# PCB_Telemetria_2020.net
KiCad netlist of a schematic drawn in EAGLE
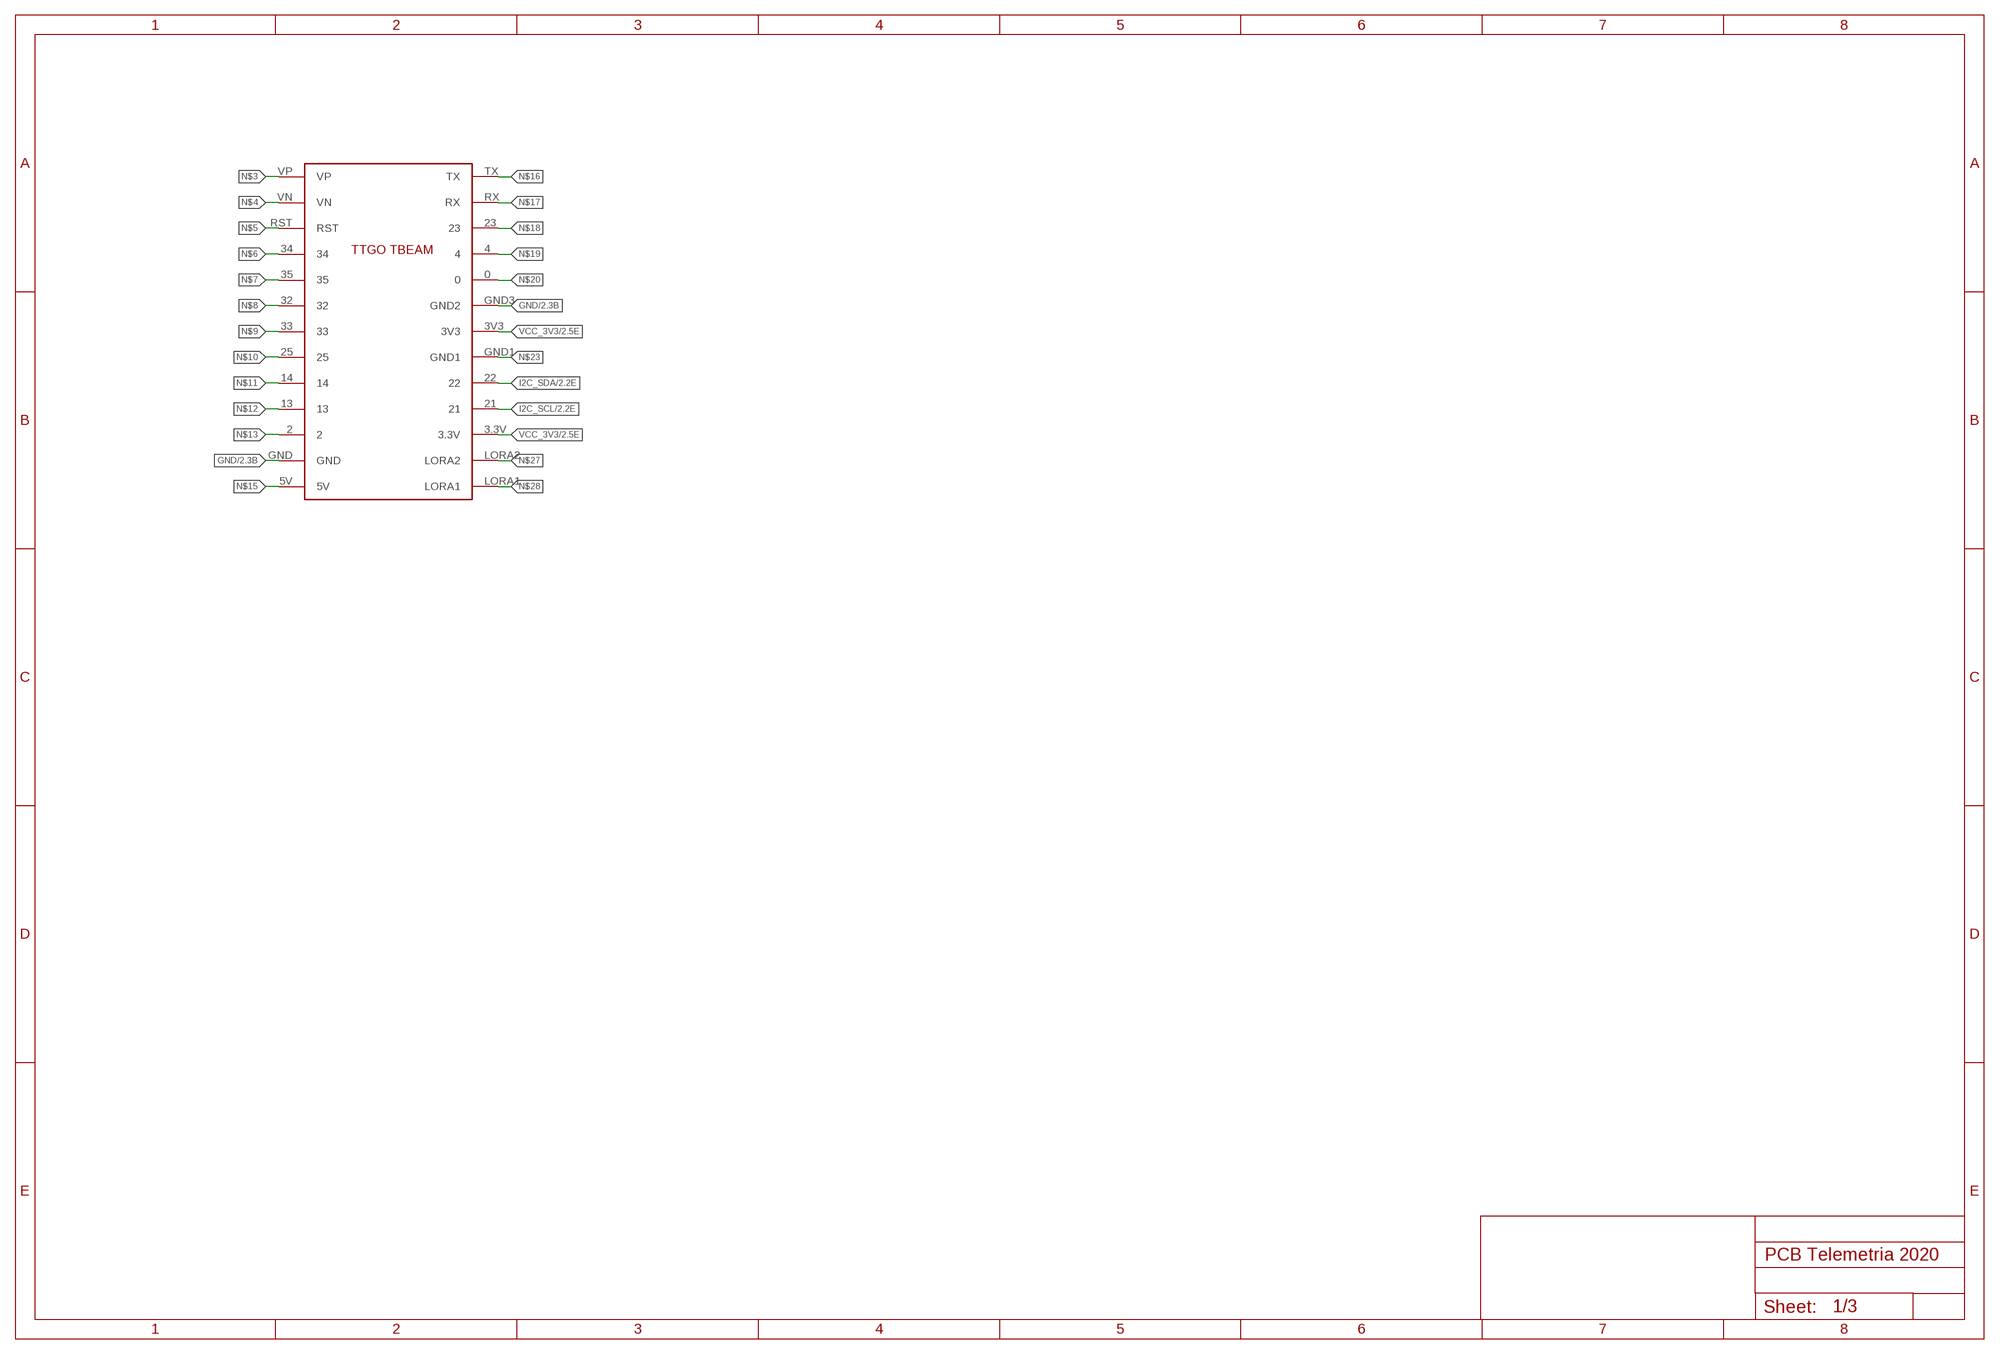
[diagram p0: schematic, sheet 1]
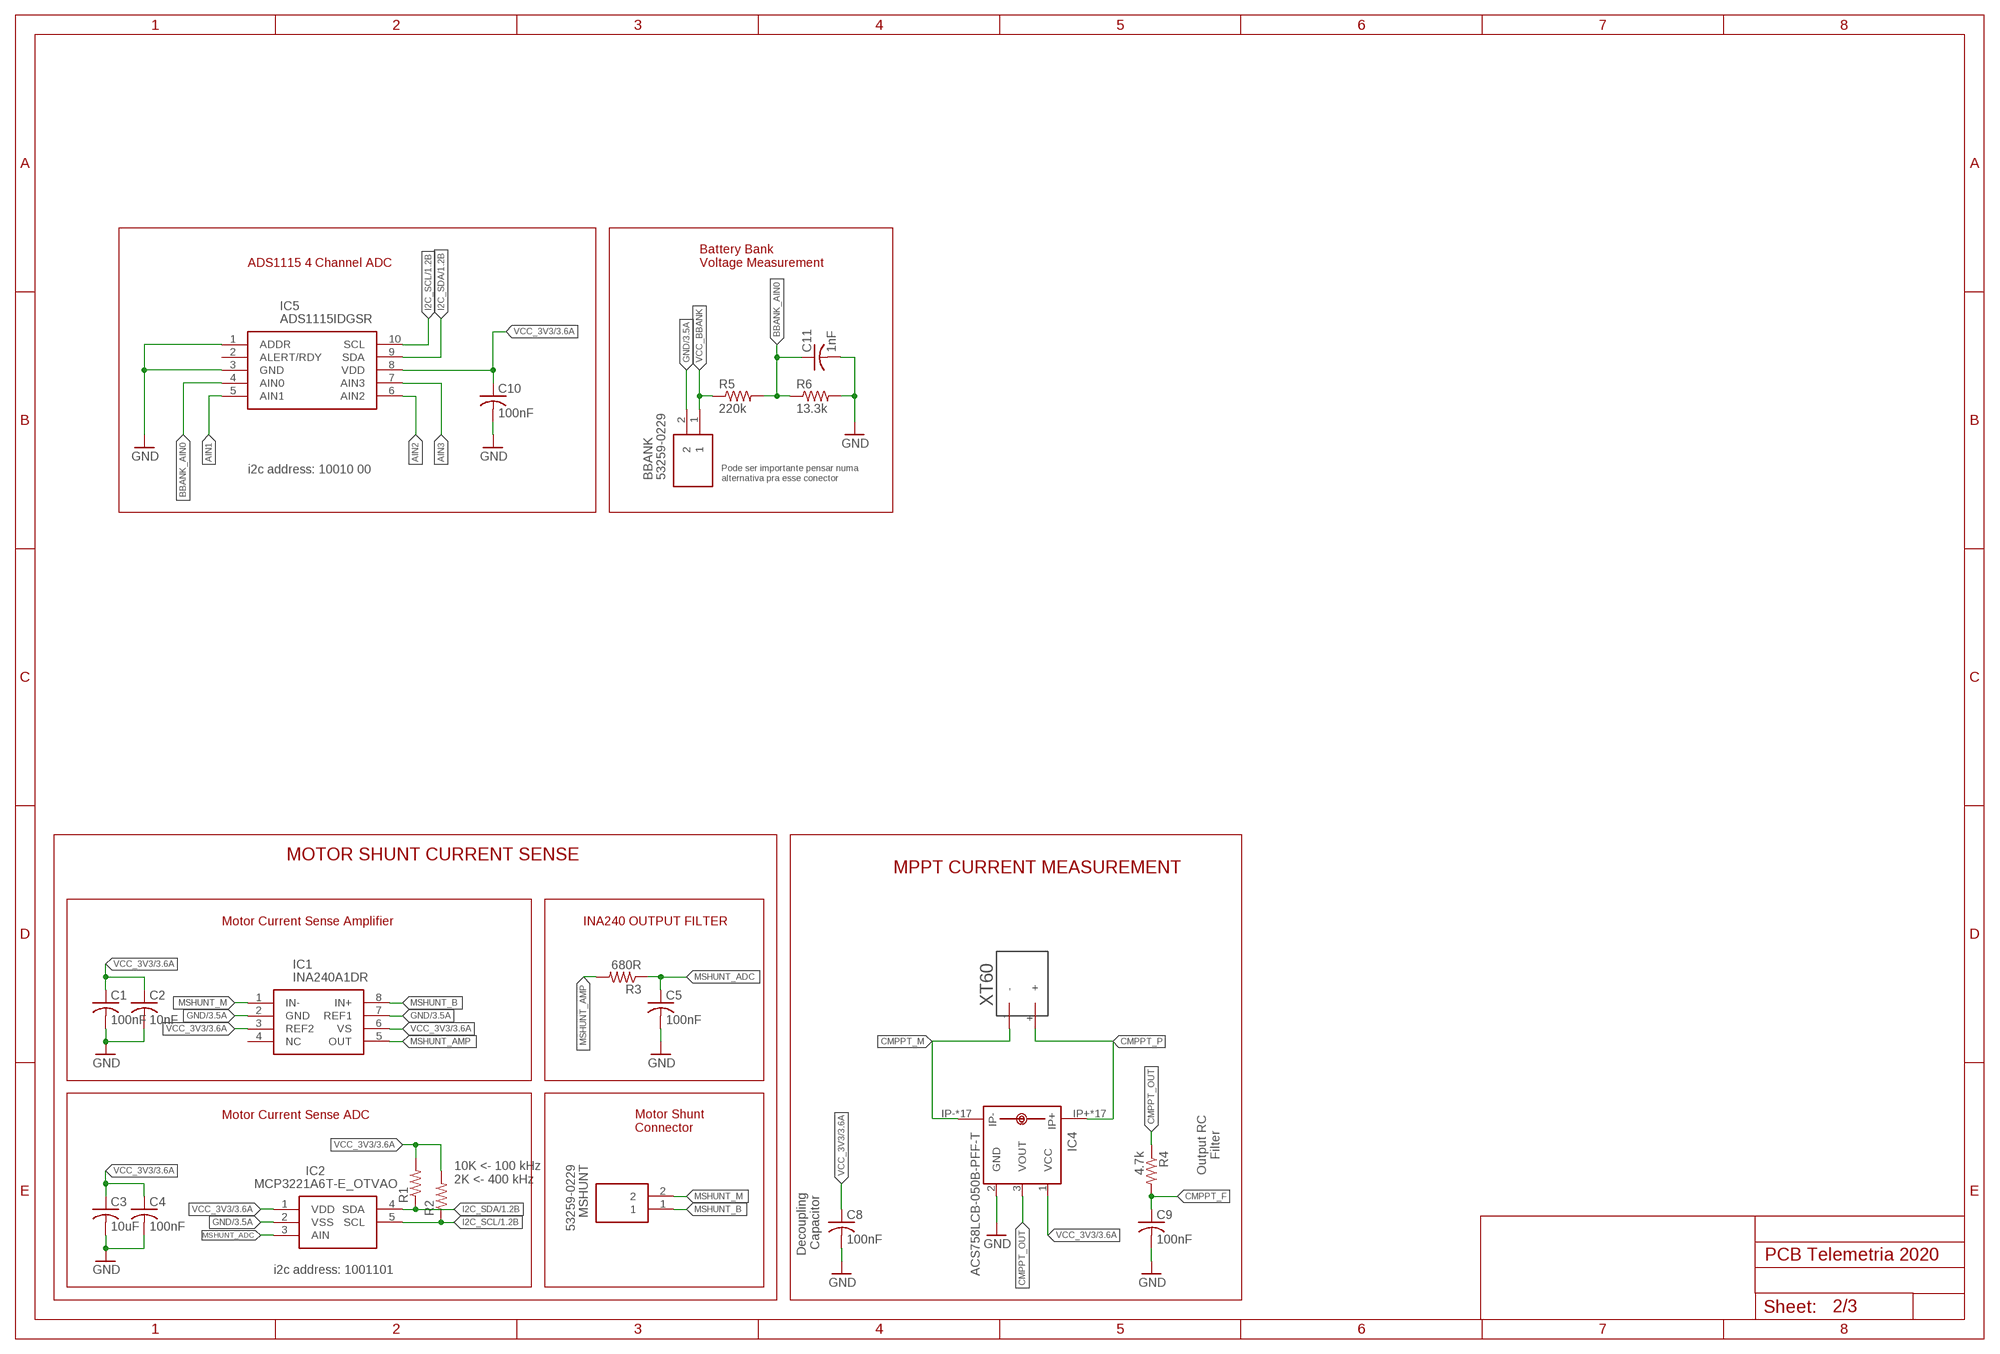
[diagram p1: schematic, sheet 2]
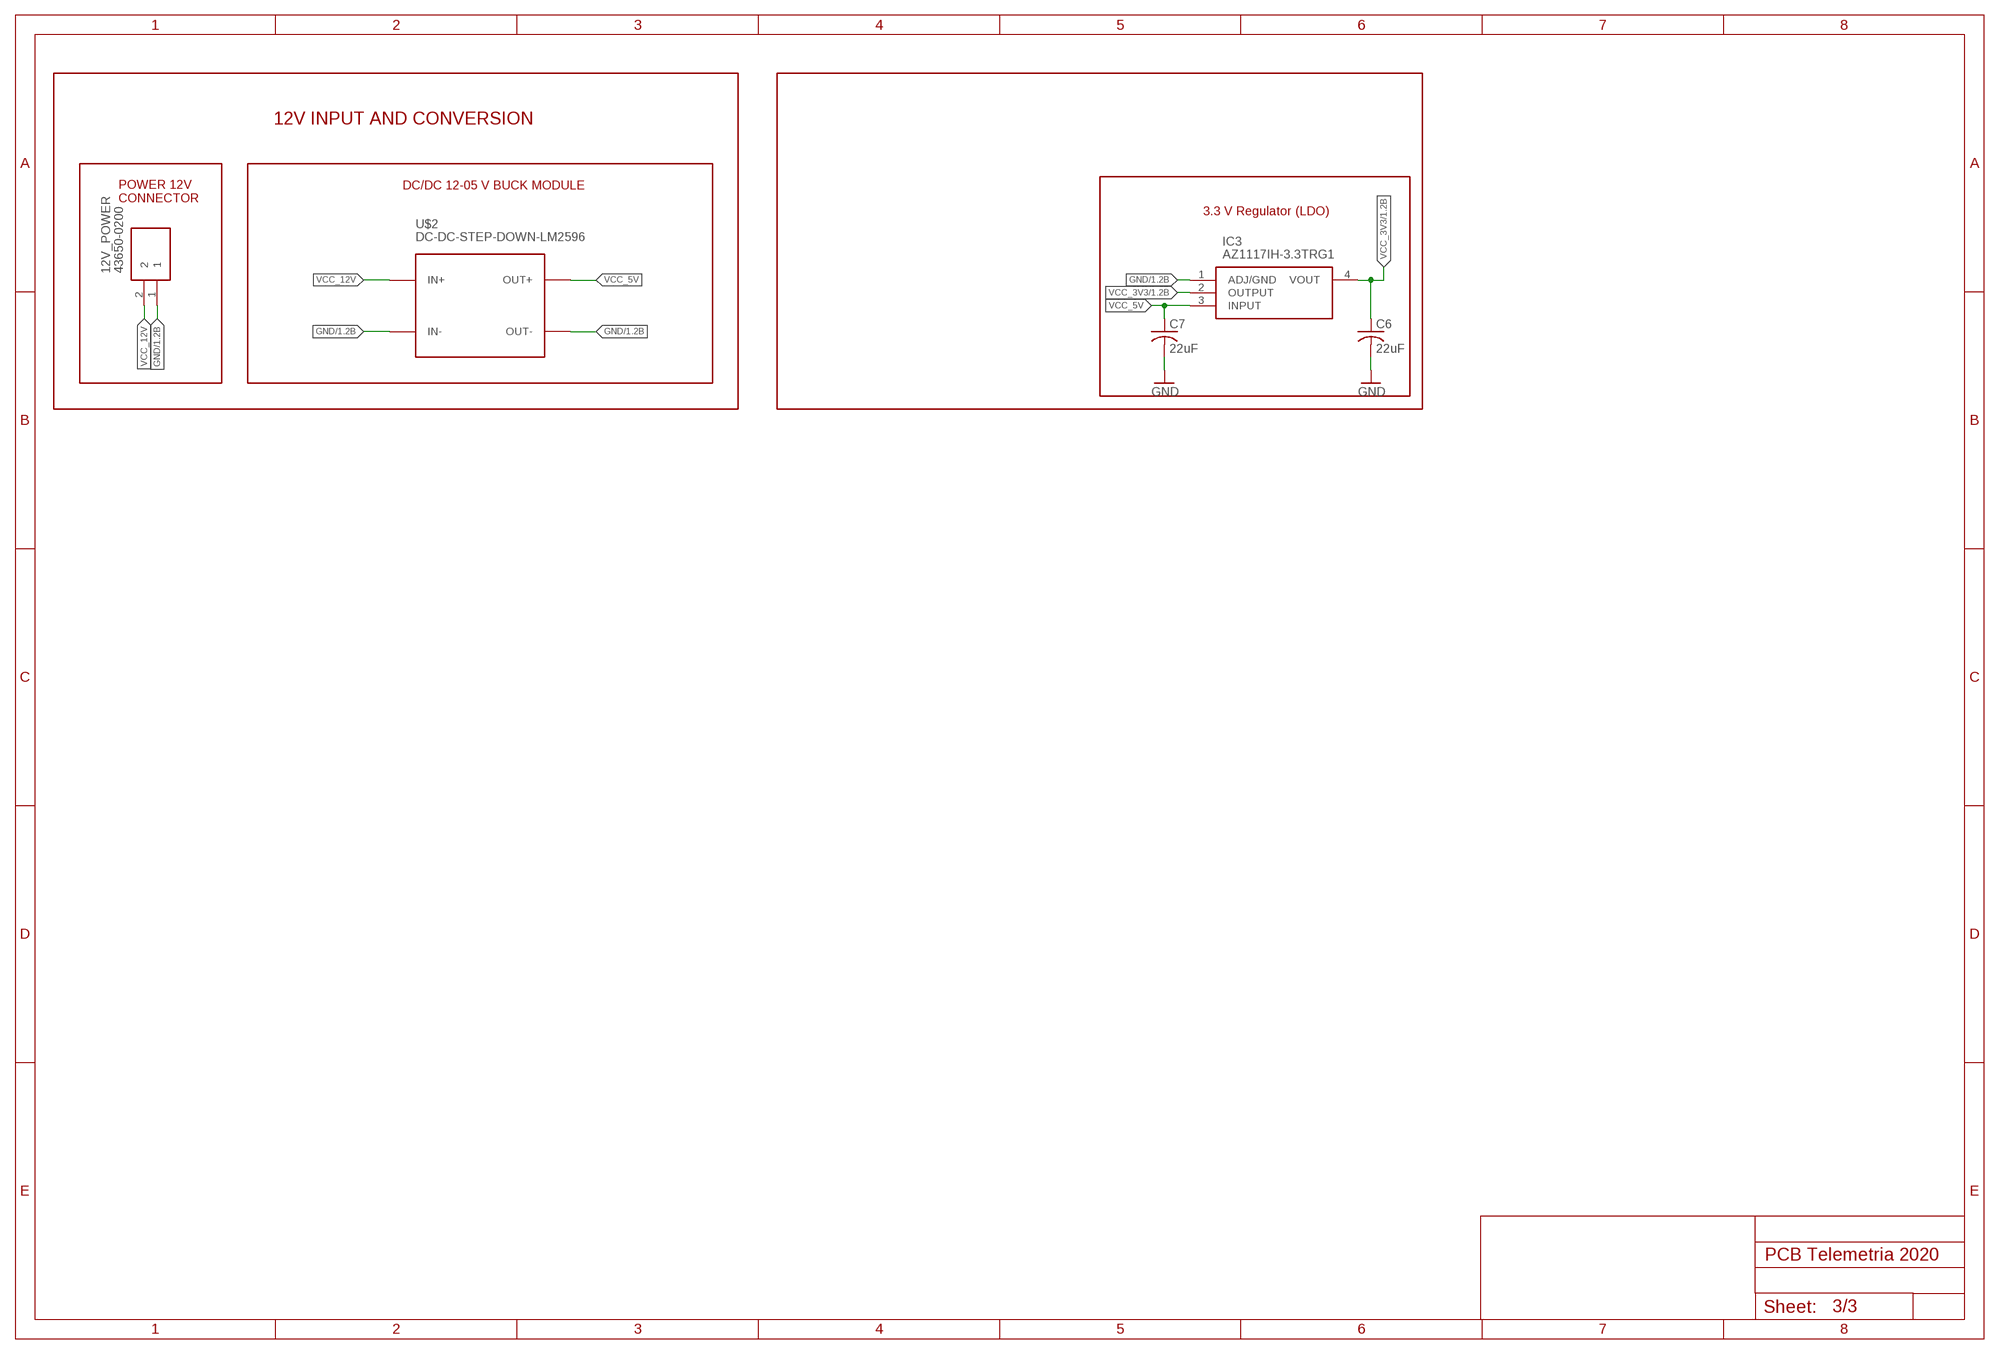
[diagram p2: schematic, sheet 3]

(export (version "E")
  (design (tool "Eeschema 10.0.6"))
  (components
    (comp (ref "12V_POWER")
      (value "43650-0200")
      (footprint "eagle-import:43650-0200")
      (fields (field (name "MOUSER_PART_NUMBER") "538-43650-0200"))
      (libsource (lib "eagle-import") (part "43650-0200"))
    )
    (comp (ref "C6")
      (value "22uF")
      (footprint "eagle-import:C0805")
      (libsource (lib "eagle-import") (part "C-USC0805"))
    )
    (comp (ref "C7")
      (value "22uF")
      (footprint "eagle-import:C0805")
      (libsource (lib "eagle-import") (part "C-USC0805"))
    )
    (comp (ref "IC3")
      (value "AZ1117IH-3.3TRG1")
      (footprint "eagle-import:SOT230P700X170-4N")
      (fields (field (name "MOUSER_PART_NUMBER") "621-AZ1117IH-3.3TRG1"))
      (libsource (lib "eagle-import") (part "AZ1117IH-3.3TRG1"))
    )
    (comp (ref "U$2")
      (value "DC-DC-STEP-DOWN-LM2596")
      (footprint "eagle-import:DC-DC-STEP-DOWN-LM2596")
      (libsource (lib "eagle-import") (part "DC-DC-STEP-DOWN-LM2596"))
    )
    (comp (ref "BBANK")
      (value "53259-0229")
      (footprint "eagle-import:0532590229")
      (fields (field (name "MOUSER_PART_NUMBER") "538-53259-0229"))
      (libsource (lib "eagle-import") (part "53259-0229"))
    )
    (comp (ref "C1")
      (value "100nF")
      (footprint "eagle-import:C0805")
      (libsource (lib "eagle-import") (part "C-USC0805"))
    )
    (comp (ref "C2")
      (value "10nF")
      (footprint "eagle-import:C0805")
      (libsource (lib "eagle-import") (part "C-USC0805"))
    )
    (comp (ref "C3")
      (value "10uF")
      (footprint "eagle-import:C0805")
      (libsource (lib "eagle-import") (part "C-USC0805"))
    )
    (comp (ref "C4")
      (value "100nF")
      (footprint "eagle-import:C0805")
      (libsource (lib "eagle-import") (part "C-USC0805"))
    )
    (comp (ref "C5")
      (value "100nF")
      (footprint "eagle-import:C0805")
      (libsource (lib "eagle-import") (part "C-USC0805"))
    )
    (comp (ref "C8")
      (value "100nF")
      (footprint "eagle-import:C0805")
      (libsource (lib "eagle-import") (part "C-USC0805"))
    )
    (comp (ref "C9")
      (value "100nF")
      (footprint "eagle-import:C0805")
      (libsource (lib "eagle-import") (part "C-USC0805"))
    )
    (comp (ref "C10")
      (value "100nF")
      (footprint "eagle-import:C0805")
      (libsource (lib "eagle-import") (part "C-USC0805"))
    )
    (comp (ref "C11")
      (value "1nF")
      (footprint "eagle-import:C0805")
      (libsource (lib "eagle-import") (part "C-USC0805"))
    )
    (comp (ref "IC1")
      (value "INA240A1DR")
      (footprint "eagle-import:SOIC127P600X175-8N")
      (fields (field (name "MOUSER_PART_NUMBER") "595-INA240A1DR"))
      (libsource (lib "eagle-import") (part "INA240A1DR"))
    )
    (comp (ref "IC2")
      (value "MCP3221A6T-E_OTVAO")
      (footprint "eagle-import:SOT95P280X145-5N")
      (fields
        (field (name "MANUFACTURER_PART_NUMBER") "MCP3221A6T-E/OTVAO")
        (field (name "MOUSER_PART_NUMBER") "579-MCP3221A6TEOTVAO")
      )
      (libsource (lib "eagle-import") (part "MCP3221A6T-E_OTVAO"))
    )
    (comp (ref "IC4")
      (value "ACS758LCB-050B-PFF-T")
      (footprint "eagle-import:CB-PFF")
      (libsource (lib "eagle-import") (part "ACS758LCB-050B-PFF-T"))
    )
    (comp (ref "IC5")
      (value "ADS1115IDGSR")
      (footprint "eagle-import:SOP50P490X110-10N")
      (fields (field (name "MOUSER_PART_NUMBER") "595-ADS1115IDGSR"))
      (libsource (lib "eagle-import") (part "ADS1115IDGSR"))
    )
    (comp (ref "MSHUNT")
      (value "53259-0229")
      (footprint "eagle-import:0532590229")
      (fields (field (name "MOUSER_PART_NUMBER") "538-53259-0229"))
      (libsource (lib "eagle-import") (part "53259-0229"))
    )
    (comp (ref "R1")
      (value "R-US_R0805")
      (footprint "eagle-import:R0805")
      (libsource (lib "eagle-import") (part "R-US_R0805"))
    )
    (comp (ref "R2")
      (value "R-US_R0805")
      (footprint "eagle-import:R0805")
      (libsource (lib "eagle-import") (part "R-US_R0805"))
    )
    (comp (ref "R3")
      (value "680R")
      (footprint "eagle-import:R0805")
      (libsource (lib "eagle-import") (part "R-US_R0805"))
    )
    (comp (ref "R4")
      (value "4.7k")
      (footprint "eagle-import:R0805")
      (libsource (lib "eagle-import") (part "R-US_R0805"))
    )
    (comp (ref "R5")
      (value "220k")
      (footprint "eagle-import:R0805")
      (libsource (lib "eagle-import") (part "R-US_R0805"))
    )
    (comp (ref "R6")
      (value "13.3k")
      (footprint "eagle-import:R0805")
      (libsource (lib "eagle-import") (part "R-US_R0805"))
    )
    (comp (ref "U$3")
      (value "XT60")
      (footprint "eagle-import:XT60")
      (libsource (lib "eagle-import") (part "XT60"))
    )
    (comp (ref "U$1")
      (value "TTGOBEAM")
      (footprint "eagle-import:TTGOBEAM")
      (libsource (lib "eagle-import") (part "TTGOBEAM"))
    )
  )
  (nets
    (net (code "1") (name "AIN1") (class "Default")
      (node (ref "IC5") (pin "5") (pinfunction "AIN1_5") (pintype "bidirectional"))
    )
    (net (code "2") (name "AIN2") (class "Default")
      (node (ref "IC5") (pin "6") (pinfunction "AIN2_6") (pintype "bidirectional"))
    )
    (net (code "3") (name "AIN3") (class "Default")
      (node (ref "IC5") (pin "7") (pinfunction "AIN3_7") (pintype "bidirectional"))
    )
    (net (code "4") (name "BBANK_AIN0") (class "Default")
      (node (ref "C11") (pin "1") (pinfunction "1_1") (pintype "passive"))
      (node (ref "IC5") (pin "4") (pinfunction "AIN0_4") (pintype "bidirectional"))
      (node (ref "R5") (pin "2") (pinfunction "2_2") (pintype "passive"))
      (node (ref "R6") (pin "1") (pinfunction "1_1") (pintype "passive"))
    )
    (net (code "5") (name "CMPPT_F") (class "Default")
      (node (ref "C9") (pin "1") (pinfunction "1_1") (pintype "passive"))
      (node (ref "R4") (pin "2") (pinfunction "2_2") (pintype "passive"))
    )
    (net (code "6") (name "CMPPT_M") (class "Default")
      (node (ref "IC4") (pin "IP-") (pinfunction "IP-_IP-") (pintype "passive"))
      (node (ref "IC4") (pin "IP-@10") (pinfunction "IP-_IP-@10") (pintype "passive"))
      (node (ref "IC4") (pin "IP-@11") (pinfunction "IP-_IP-@11") (pintype "passive"))
      (node (ref "IC4") (pin "IP-@12") (pinfunction "IP-_IP-@12") (pintype "passive"))
      (node (ref "IC4") (pin "IP-@13") (pinfunction "IP-_IP-@13") (pintype "passive"))
      (node (ref "IC4") (pin "IP-@14") (pinfunction "IP-_IP-@14") (pintype "passive"))
      (node (ref "IC4") (pin "IP-@15") (pinfunction "IP-_IP-@15") (pintype "passive"))
      (node (ref "IC4") (pin "IP-@16") (pinfunction "IP-_IP-@16") (pintype "passive"))
      (node (ref "IC4") (pin "IP-@17") (pinfunction "IP-_IP-@17") (pintype "passive"))
      (node (ref "IC4") (pin "IP-@2") (pinfunction "IP-_IP-@2") (pintype "passive"))
      (node (ref "IC4") (pin "IP-@3") (pinfunction "IP-_IP-@3") (pintype "passive"))
      (node (ref "IC4") (pin "IP-@4") (pinfunction "IP-_IP-@4") (pintype "passive"))
      (node (ref "IC4") (pin "IP-@5") (pinfunction "IP-_IP-@5") (pintype "passive"))
      (node (ref "IC4") (pin "IP-@6") (pinfunction "IP-_IP-@6") (pintype "passive"))
      (node (ref "IC4") (pin "IP-@7") (pinfunction "IP-_IP-@7") (pintype "passive"))
      (node (ref "IC4") (pin "IP-@8") (pinfunction "IP-_IP-@8") (pintype "passive"))
      (node (ref "IC4") (pin "IP-@9") (pinfunction "IP-_IP-@9") (pintype "passive"))
      (node (ref "U$3") (pin "-") (pinfunction "-_-") (pintype "bidirectional"))
    )
    (net (code "7") (name "CMPPT_OUT") (class "Default")
      (node (ref "IC4") (pin "3") (pinfunction "VOUT_3") (pintype "output"))
      (node (ref "R4") (pin "1") (pinfunction "1_1") (pintype "passive"))
    )
    (net (code "8") (name "CMPPT_P") (class "Default")
      (node (ref "IC4") (pin "IP+") (pinfunction "IP+_IP+") (pintype "passive"))
      (node (ref "IC4") (pin "IP+@10") (pinfunction "IP+_IP+@10") (pintype "passive"))
      (node (ref "IC4") (pin "IP+@11") (pinfunction "IP+_IP+@11") (pintype "passive"))
      (node (ref "IC4") (pin "IP+@12") (pinfunction "IP+_IP+@12") (pintype "passive"))
      (node (ref "IC4") (pin "IP+@13") (pinfunction "IP+_IP+@13") (pintype "passive"))
      (node (ref "IC4") (pin "IP+@14") (pinfunction "IP+_IP+@14") (pintype "passive"))
      (node (ref "IC4") (pin "IP+@15") (pinfunction "IP+_IP+@15") (pintype "passive"))
      (node (ref "IC4") (pin "IP+@16") (pinfunction "IP+_IP+@16") (pintype "passive"))
      (node (ref "IC4") (pin "IP+@17") (pinfunction "IP+_IP+@17") (pintype "passive"))
      (node (ref "IC4") (pin "IP+@2") (pinfunction "IP+_IP+@2") (pintype "passive"))
      (node (ref "IC4") (pin "IP+@3") (pinfunction "IP+_IP+@3") (pintype "passive"))
      (node (ref "IC4") (pin "IP+@4") (pinfunction "IP+_IP+@4") (pintype "passive"))
      (node (ref "IC4") (pin "IP+@5") (pinfunction "IP+_IP+@5") (pintype "passive"))
      (node (ref "IC4") (pin "IP+@6") (pinfunction "IP+_IP+@6") (pintype "passive"))
      (node (ref "IC4") (pin "IP+@7") (pinfunction "IP+_IP+@7") (pintype "passive"))
      (node (ref "IC4") (pin "IP+@8") (pinfunction "IP+_IP+@8") (pintype "passive"))
      (node (ref "IC4") (pin "IP+@9") (pinfunction "IP+_IP+@9") (pintype "passive"))
      (node (ref "U$3") (pin "+") (pinfunction "+_+") (pintype "bidirectional"))
    )
    (net (code "9") (name "GND") (class "Default")
      (node (ref "12V_POWER") (pin "1") (pinfunction "1_1") (pintype "bidirectional"))
      (node (ref "BBANK") (pin "2") (pinfunction "2_2") (pintype "bidirectional"))
      (node (ref "C1") (pin "2") (pinfunction "2_2") (pintype "passive"))
      (node (ref "C10") (pin "2") (pinfunction "2_2") (pintype "passive"))
      (node (ref "C11") (pin "2") (pinfunction "2_2") (pintype "passive"))
      (node (ref "C2") (pin "2") (pinfunction "2_2") (pintype "passive"))
      (node (ref "C3") (pin "2") (pinfunction "2_2") (pintype "passive"))
      (node (ref "C4") (pin "2") (pinfunction "2_2") (pintype "passive"))
      (node (ref "C5") (pin "2") (pinfunction "2_2") (pintype "passive"))
      (node (ref "C6") (pin "2") (pinfunction "2_2") (pintype "passive"))
      (node (ref "C7") (pin "2") (pinfunction "2_2") (pintype "passive"))
      (node (ref "C8") (pin "2") (pinfunction "2_2") (pintype "passive"))
      (node (ref "C9") (pin "2") (pinfunction "2_2") (pintype "passive"))
      (node (ref "IC1") (pin "2") (pinfunction "GND_2") (pintype "bidirectional"))
      (node (ref "IC1") (pin "7") (pinfunction "REF1_7") (pintype "bidirectional"))
      (node (ref "IC2") (pin "2") (pinfunction "VSS_2") (pintype "bidirectional"))
      (node (ref "IC3") (pin "1") (pinfunction "ADJ/GND_1") (pintype "bidirectional"))
      (node (ref "IC4") (pin "2") (pinfunction "GND_2") (pintype "power_in"))
      (node (ref "IC5") (pin "1") (pinfunction "ADDR_1") (pintype "bidirectional"))
      (node (ref "IC5") (pin "3") (pinfunction "GND_3") (pintype "bidirectional"))
      (node (ref "R6") (pin "2") (pinfunction "2_2") (pintype "passive"))
      (node (ref "U$1") (pin "GND") (pinfunction "GND_GND") (pintype "bidirectional"))
      (node (ref "U$1") (pin "GND3") (pinfunction "GND2_GND3") (pintype "bidirectional"))
      (node (ref "U$2") (pin "IN-") (pinfunction "IN-_IN-") (pintype "bidirectional"))
      (node (ref "U$2") (pin "OUT-") (pinfunction "OUT-_OUT-") (pintype "bidirectional"))
    )
    (net (code "10") (name "I2C_SCL") (class "Default")
      (node (ref "IC2") (pin "5") (pinfunction "SCL_5") (pintype "bidirectional"))
      (node (ref "IC5") (pin "10") (pinfunction "SCL_10") (pintype "bidirectional"))
      (node (ref "R2") (pin "1") (pinfunction "1_1") (pintype "passive"))
      (node (ref "U$1") (pin "21") (pinfunction "21_21") (pintype "bidirectional"))
    )
    (net (code "11") (name "I2C_SDA") (class "Default")
      (node (ref "IC2") (pin "4") (pinfunction "SDA_4") (pintype "bidirectional"))
      (node (ref "IC5") (pin "9") (pinfunction "SDA_9") (pintype "bidirectional"))
      (node (ref "R1") (pin "1") (pinfunction "1_1") (pintype "passive"))
      (node (ref "U$1") (pin "22") (pinfunction "22_22") (pintype "bidirectional"))
    )
    (net (code "12") (name "MSHUNT_ADC") (class "Default")
      (node (ref "C5") (pin "1") (pinfunction "1_1") (pintype "passive"))
      (node (ref "IC2") (pin "3") (pinfunction "AIN_3") (pintype "bidirectional"))
      (node (ref "R3") (pin "1") (pinfunction "1_1") (pintype "passive"))
    )
    (net (code "13") (name "MSHUNT_AMP") (class "Default")
      (node (ref "IC1") (pin "5") (pinfunction "OUT_5") (pintype "bidirectional"))
      (node (ref "R3") (pin "2") (pinfunction "2_2") (pintype "passive"))
    )
    (net (code "14") (name "MSHUNT_B") (class "Default")
      (node (ref "IC1") (pin "8") (pinfunction "IN+_8") (pintype "bidirectional"))
      (node (ref "MSHUNT") (pin "1") (pinfunction "1_1") (pintype "bidirectional"))
    )
    (net (code "15") (name "MSHUNT_M") (class "Default")
      (node (ref "IC1") (pin "1") (pinfunction "IN-_1") (pintype "bidirectional"))
      (node (ref "MSHUNT") (pin "2") (pinfunction "2_2") (pintype "bidirectional"))
    )
    (net (code "16") (name "N$3") (class "Default")
      (node (ref "U$1") (pin "VP") (pinfunction "VP_VP") (pintype "bidirectional"))
    )
    (net (code "17") (name "N$4") (class "Default")
      (node (ref "U$1") (pin "VN") (pinfunction "VN_VN") (pintype "bidirectional"))
    )
    (net (code "18") (name "N$5") (class "Default")
      (node (ref "U$1") (pin "RST") (pinfunction "RST_RST") (pintype "bidirectional"))
    )
    (net (code "19") (name "N$6") (class "Default")
      (node (ref "U$1") (pin "34") (pinfunction "34_34") (pintype "bidirectional"))
    )
    (net (code "20") (name "N$7") (class "Default")
      (node (ref "U$1") (pin "35") (pinfunction "35_35") (pintype "bidirectional"))
    )
    (net (code "21") (name "N$8") (class "Default")
      (node (ref "U$1") (pin "32") (pinfunction "32_32") (pintype "bidirectional"))
    )
    (net (code "22") (name "N$9") (class "Default")
      (node (ref "U$1") (pin "33") (pinfunction "33_33") (pintype "bidirectional"))
    )
    (net (code "23") (name "N$10") (class "Default")
      (node (ref "U$1") (pin "25") (pinfunction "25_25") (pintype "bidirectional"))
    )
    (net (code "24") (name "N$11") (class "Default")
      (node (ref "U$1") (pin "14") (pinfunction "14_14") (pintype "bidirectional"))
    )
    (net (code "25") (name "N$12") (class "Default")
      (node (ref "U$1") (pin "13") (pinfunction "13_13") (pintype "bidirectional"))
    )
    (net (code "26") (name "N$13") (class "Default")
      (node (ref "U$1") (pin "2") (pinfunction "2_2") (pintype "bidirectional"))
    )
    (net (code "27") (name "N$15") (class "Default")
      (node (ref "U$1") (pin "5V") (pinfunction "5V_5V") (pintype "bidirectional"))
    )
    (net (code "28") (name "N$16") (class "Default")
      (node (ref "U$1") (pin "TX") (pinfunction "TX_TX") (pintype "bidirectional"))
    )
    (net (code "29") (name "N$17") (class "Default")
      (node (ref "U$1") (pin "RX") (pinfunction "RX_RX") (pintype "bidirectional"))
    )
    (net (code "30") (name "N$18") (class "Default")
      (node (ref "U$1") (pin "23") (pinfunction "23_23") (pintype "bidirectional"))
    )
    (net (code "31") (name "N$19") (class "Default")
      (node (ref "U$1") (pin "4") (pinfunction "4_4") (pintype "bidirectional"))
    )
    (net (code "32") (name "N$20") (class "Default")
      (node (ref "U$1") (pin "0") (pinfunction "0_0") (pintype "bidirectional"))
    )
    (net (code "33") (name "N$23") (class "Default")
      (node (ref "U$1") (pin "GND1") (pinfunction "GND1_GND1") (pintype "bidirectional"))
    )
    (net (code "34") (name "N$27") (class "Default")
      (node (ref "U$1") (pin "LORA2") (pinfunction "LORA2_LORA2") (pintype "bidirectional"))
    )
    (net (code "35") (name "N$28") (class "Default")
      (node (ref "U$1") (pin "LORA1") (pinfunction "LORA1_LORA1") (pintype "bidirectional"))
    )
    (net (code "36") (name "VCC_3V3") (class "Default")
      (node (ref "C1") (pin "1") (pinfunction "1_1") (pintype "passive"))
      (node (ref "C10") (pin "1") (pinfunction "1_1") (pintype "passive"))
      (node (ref "C2") (pin "1") (pinfunction "1_1") (pintype "passive"))
      (node (ref "C3") (pin "1") (pinfunction "1_1") (pintype "passive"))
      (node (ref "C4") (pin "1") (pinfunction "1_1") (pintype "passive"))
      (node (ref "C6") (pin "1") (pinfunction "1_1") (pintype "passive"))
      (node (ref "C8") (pin "1") (pinfunction "1_1") (pintype "passive"))
      (node (ref "IC1") (pin "3") (pinfunction "REF2_3") (pintype "bidirectional"))
      (node (ref "IC1") (pin "6") (pinfunction "VS_6") (pintype "bidirectional"))
      (node (ref "IC2") (pin "1") (pinfunction "VDD_1") (pintype "bidirectional"))
      (node (ref "IC3") (pin "2") (pinfunction "OUTPUT_2") (pintype "bidirectional"))
      (node (ref "IC3") (pin "4") (pinfunction "VOUT_4") (pintype "bidirectional"))
      (node (ref "IC4") (pin "1") (pinfunction "VCC_1") (pintype "power_in"))
      (node (ref "IC5") (pin "8") (pinfunction "VDD_8") (pintype "bidirectional"))
      (node (ref "R1") (pin "2") (pinfunction "2_2") (pintype "passive"))
      (node (ref "R2") (pin "2") (pinfunction "2_2") (pintype "passive"))
      (node (ref "U$1") (pin "3.3V") (pinfunction "3.3V_3.3V") (pintype "bidirectional"))
      (node (ref "U$1") (pin "3V3") (pinfunction "3V3_3V3") (pintype "bidirectional"))
    )
    (net (code "37") (name "VCC_5V") (class "Default")
      (node (ref "C7") (pin "1") (pinfunction "1_1") (pintype "passive"))
      (node (ref "IC3") (pin "3") (pinfunction "INPUT_3") (pintype "bidirectional"))
      (node (ref "U$2") (pin "OUT+") (pinfunction "OUT+_OUT+") (pintype "bidirectional"))
    )
    (net (code "38") (name "VCC_12V") (class "Default")
      (node (ref "12V_POWER") (pin "2") (pinfunction "2_2") (pintype "bidirectional"))
      (node (ref "U$2") (pin "IN+") (pinfunction "IN+_IN+") (pintype "bidirectional"))
    )
    (net (code "39") (name "VCC_BBANK") (class "Default")
      (node (ref "BBANK") (pin "1") (pinfunction "1_1") (pintype "bidirectional"))
      (node (ref "R5") (pin "1") (pinfunction "1_1") (pintype "passive"))
    )
    (net (code "40") (name "unconnected-(IC1-NC-Pad4)") (class "Default")
      (node (ref "IC1") (pin "4") (pinfunction "NC_4") (pintype "no_connect"))
    )
    (net (code "41") (name "unconnected-(IC5-ALERT{slash}RDY-Pad2)") (class "Default")
      (node (ref "IC5") (pin "2") (pinfunction "ALERT/RDY_2") (pintype "bidirectional"))
    )
  )
)
